# Iridium_9603_Beacon.net
KiCad netlist of a schematic drawn in EAGLE
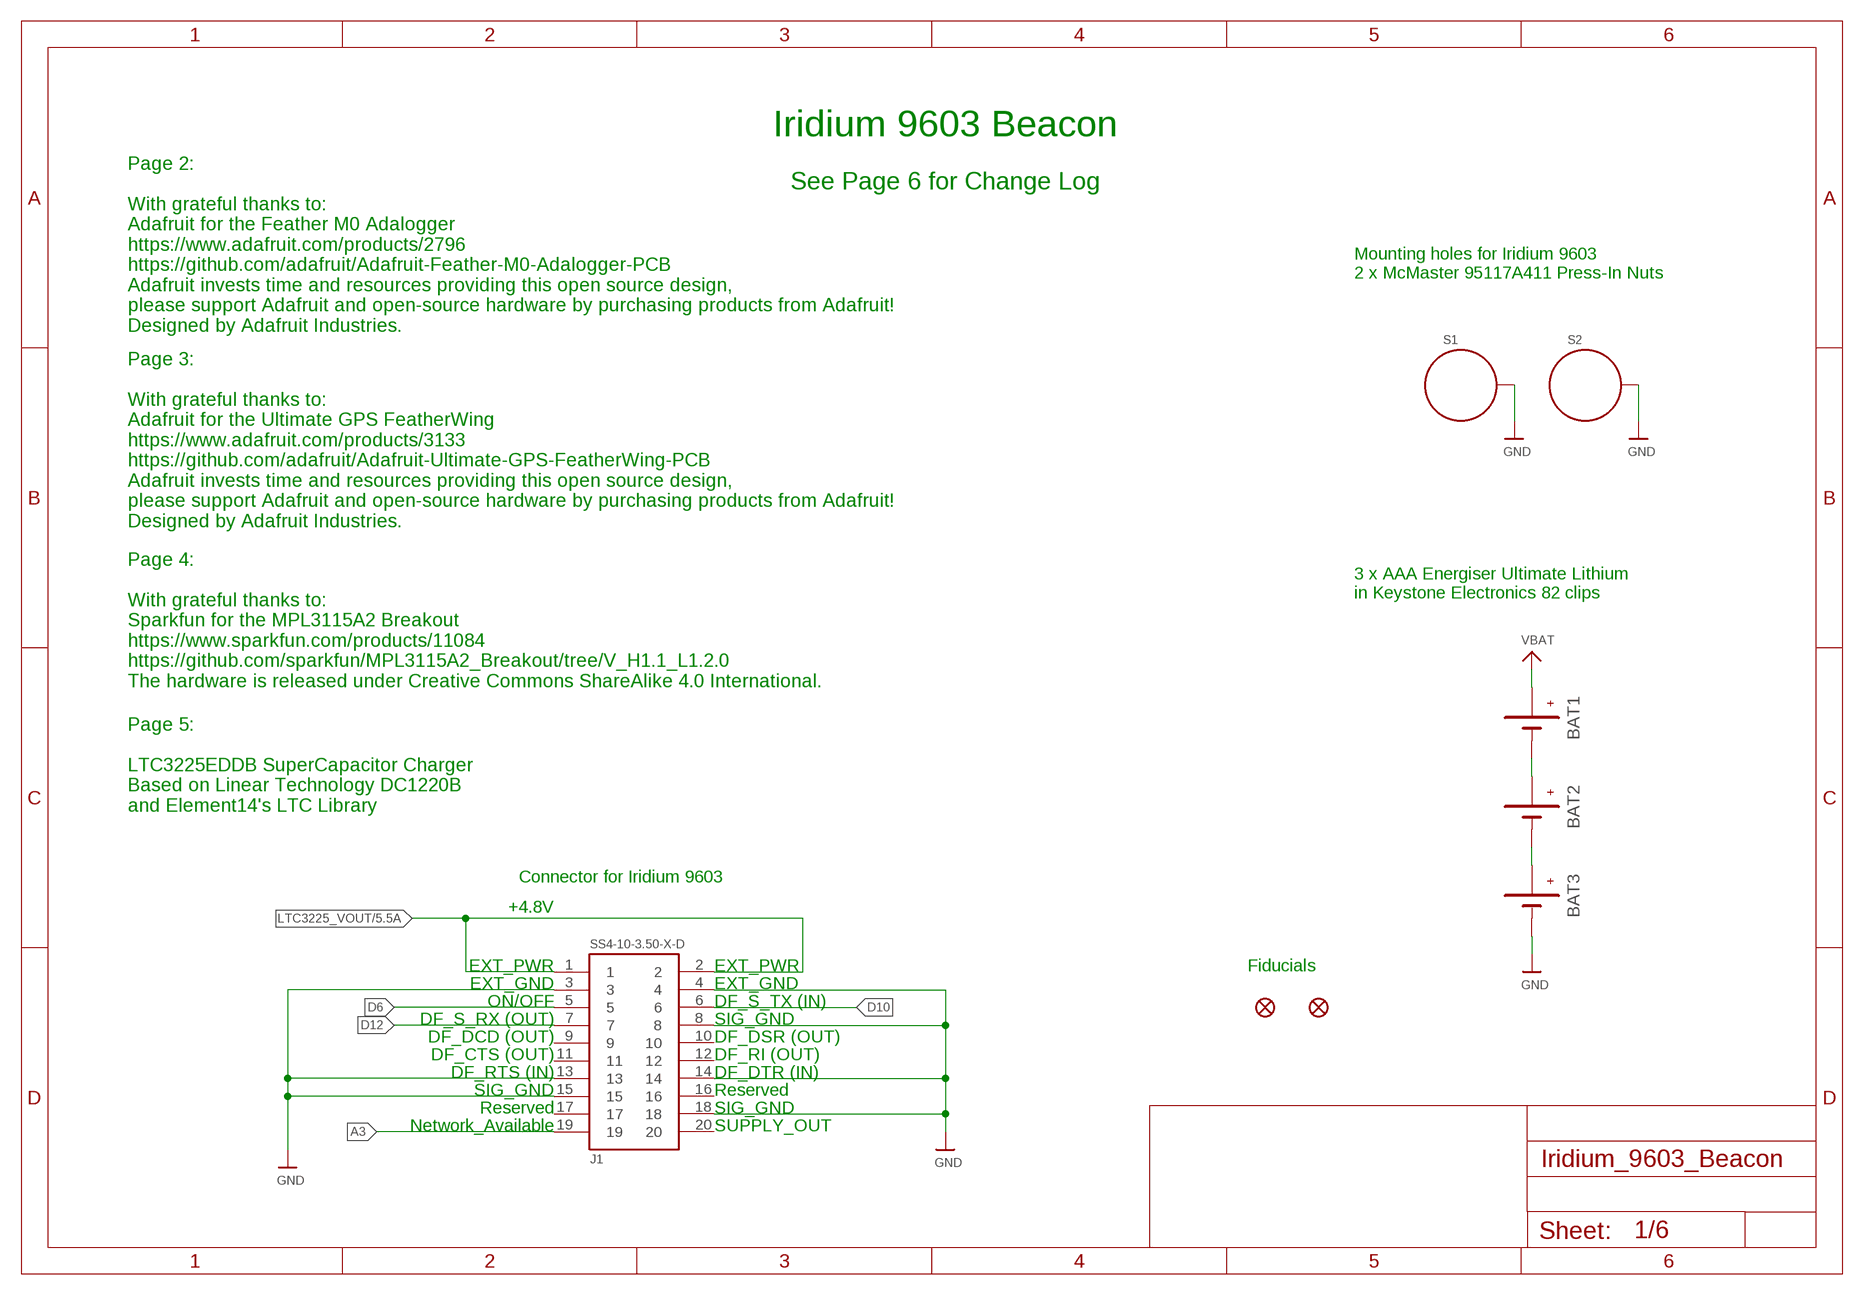
[diagram p0: schematic, sheet 1]
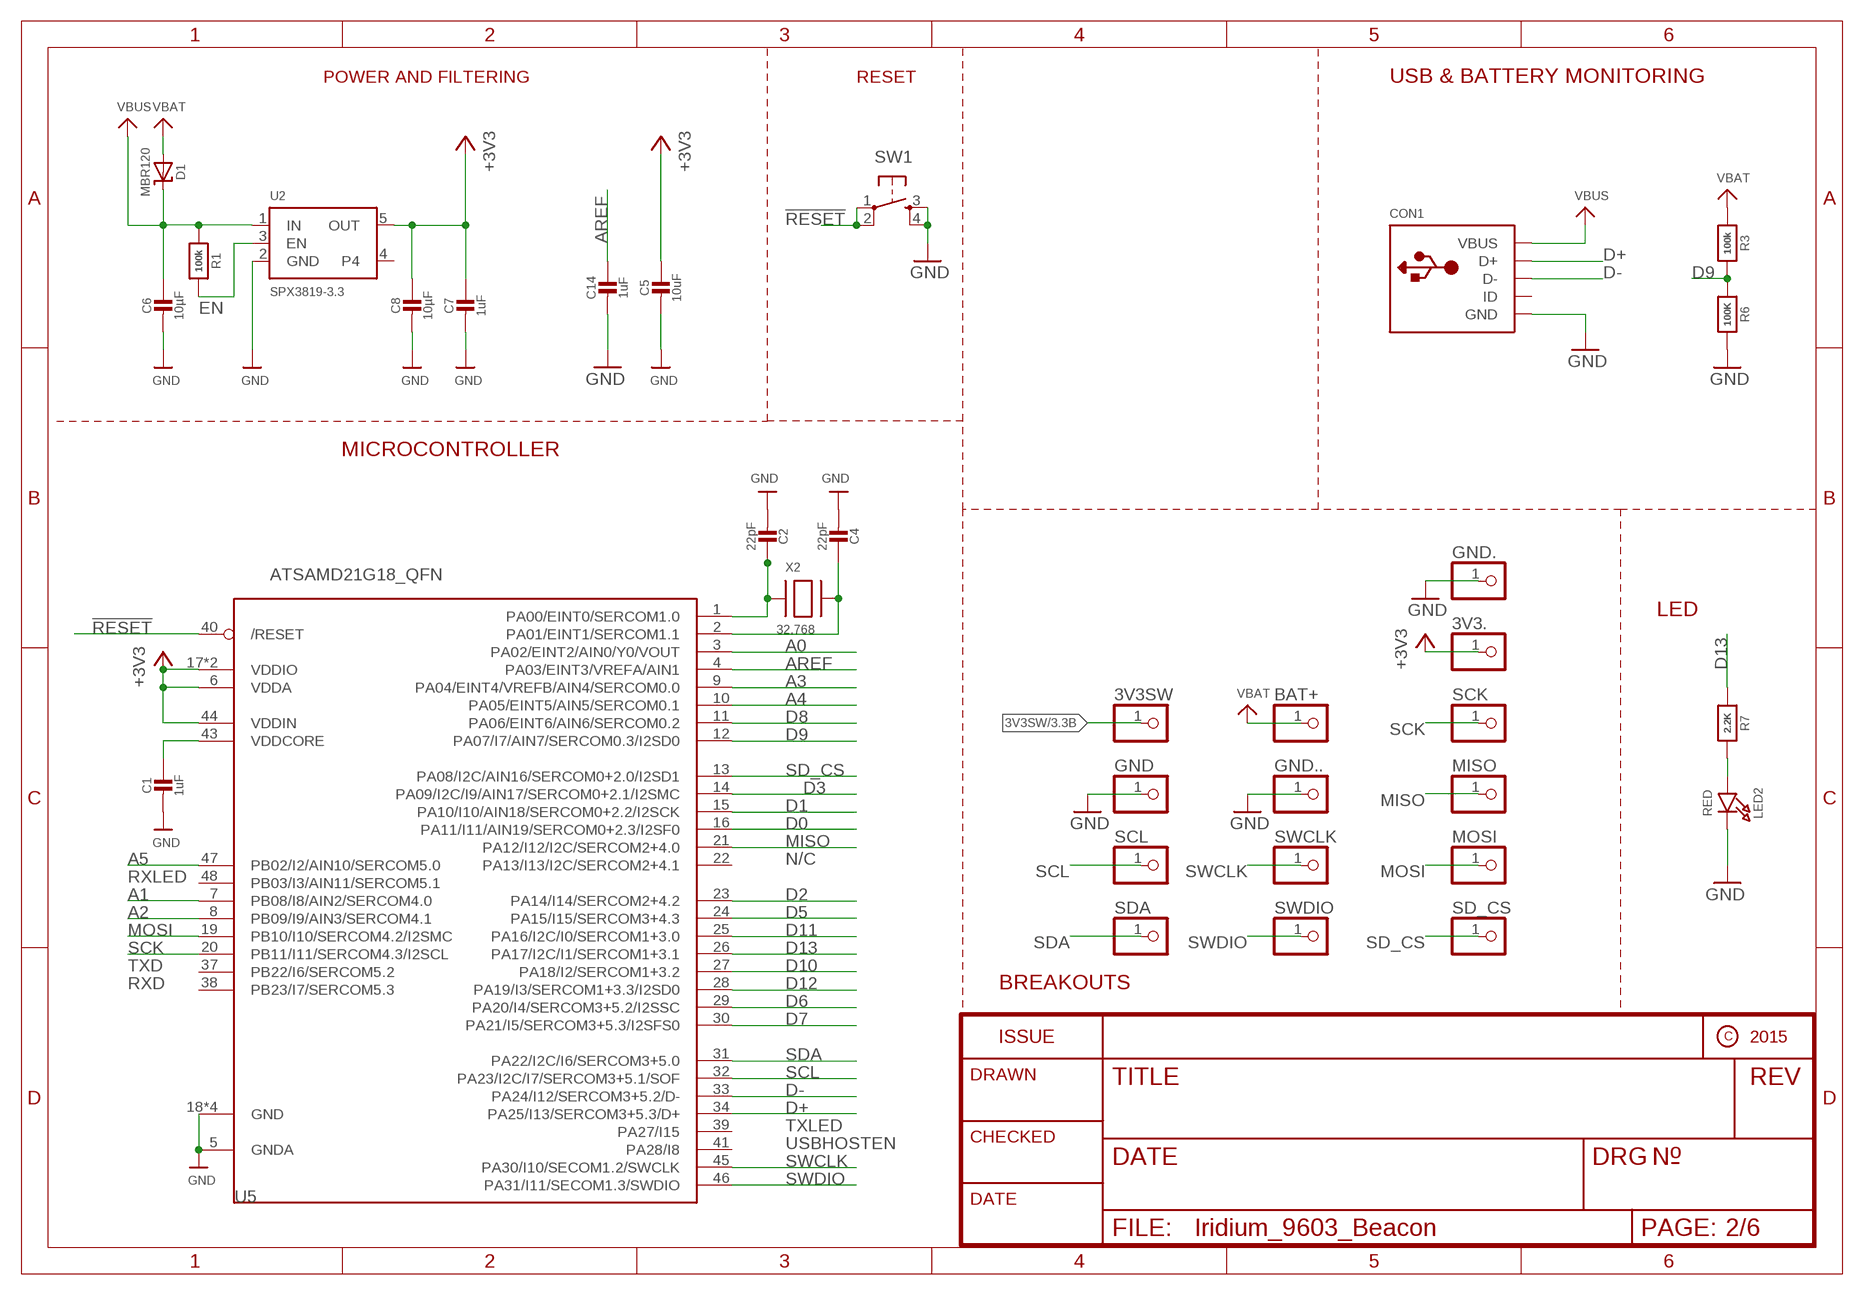
[diagram p1: schematic, sheet 2]
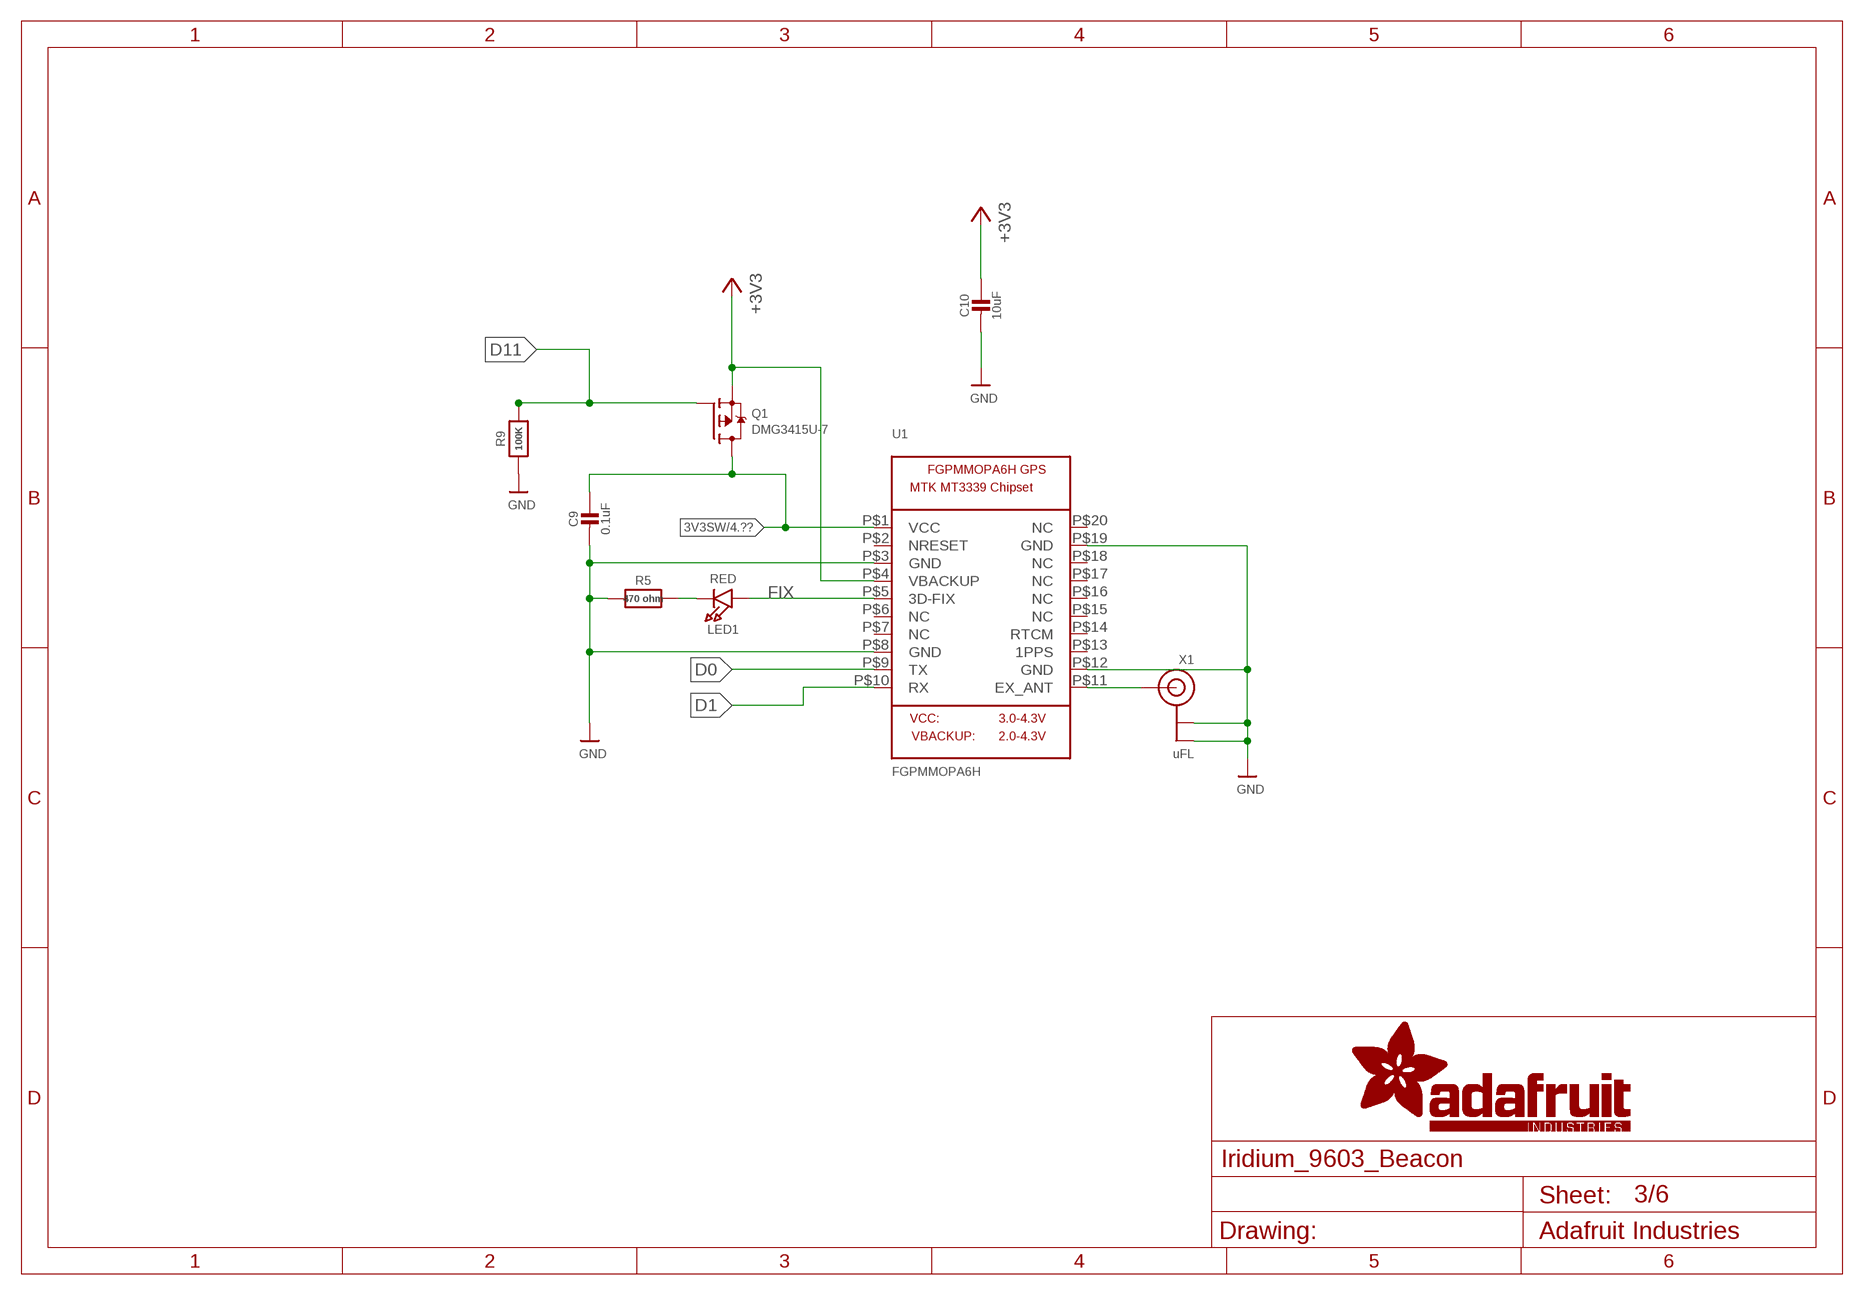
[diagram p2: schematic, sheet 3]
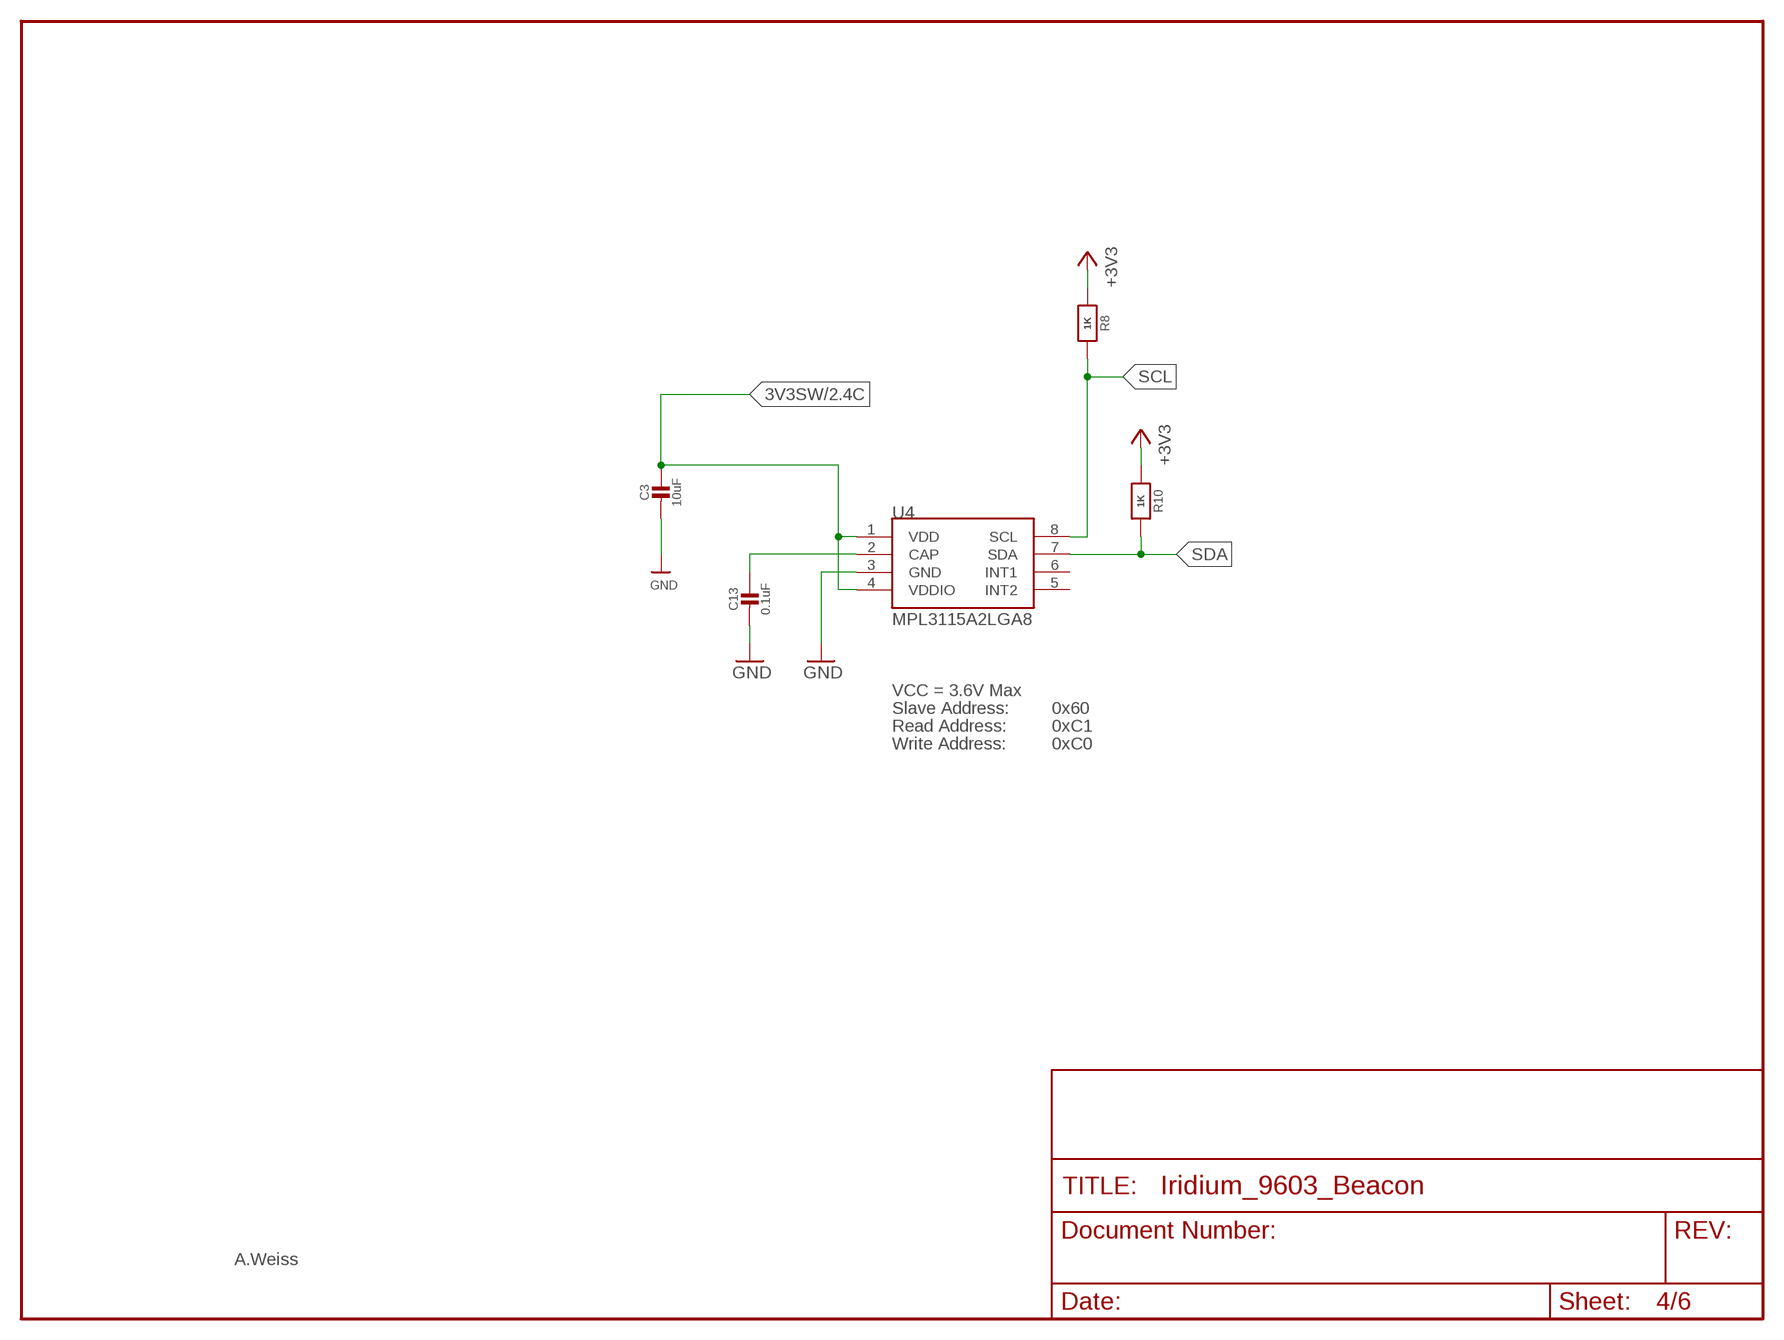
[diagram p3: schematic, sheet 4]
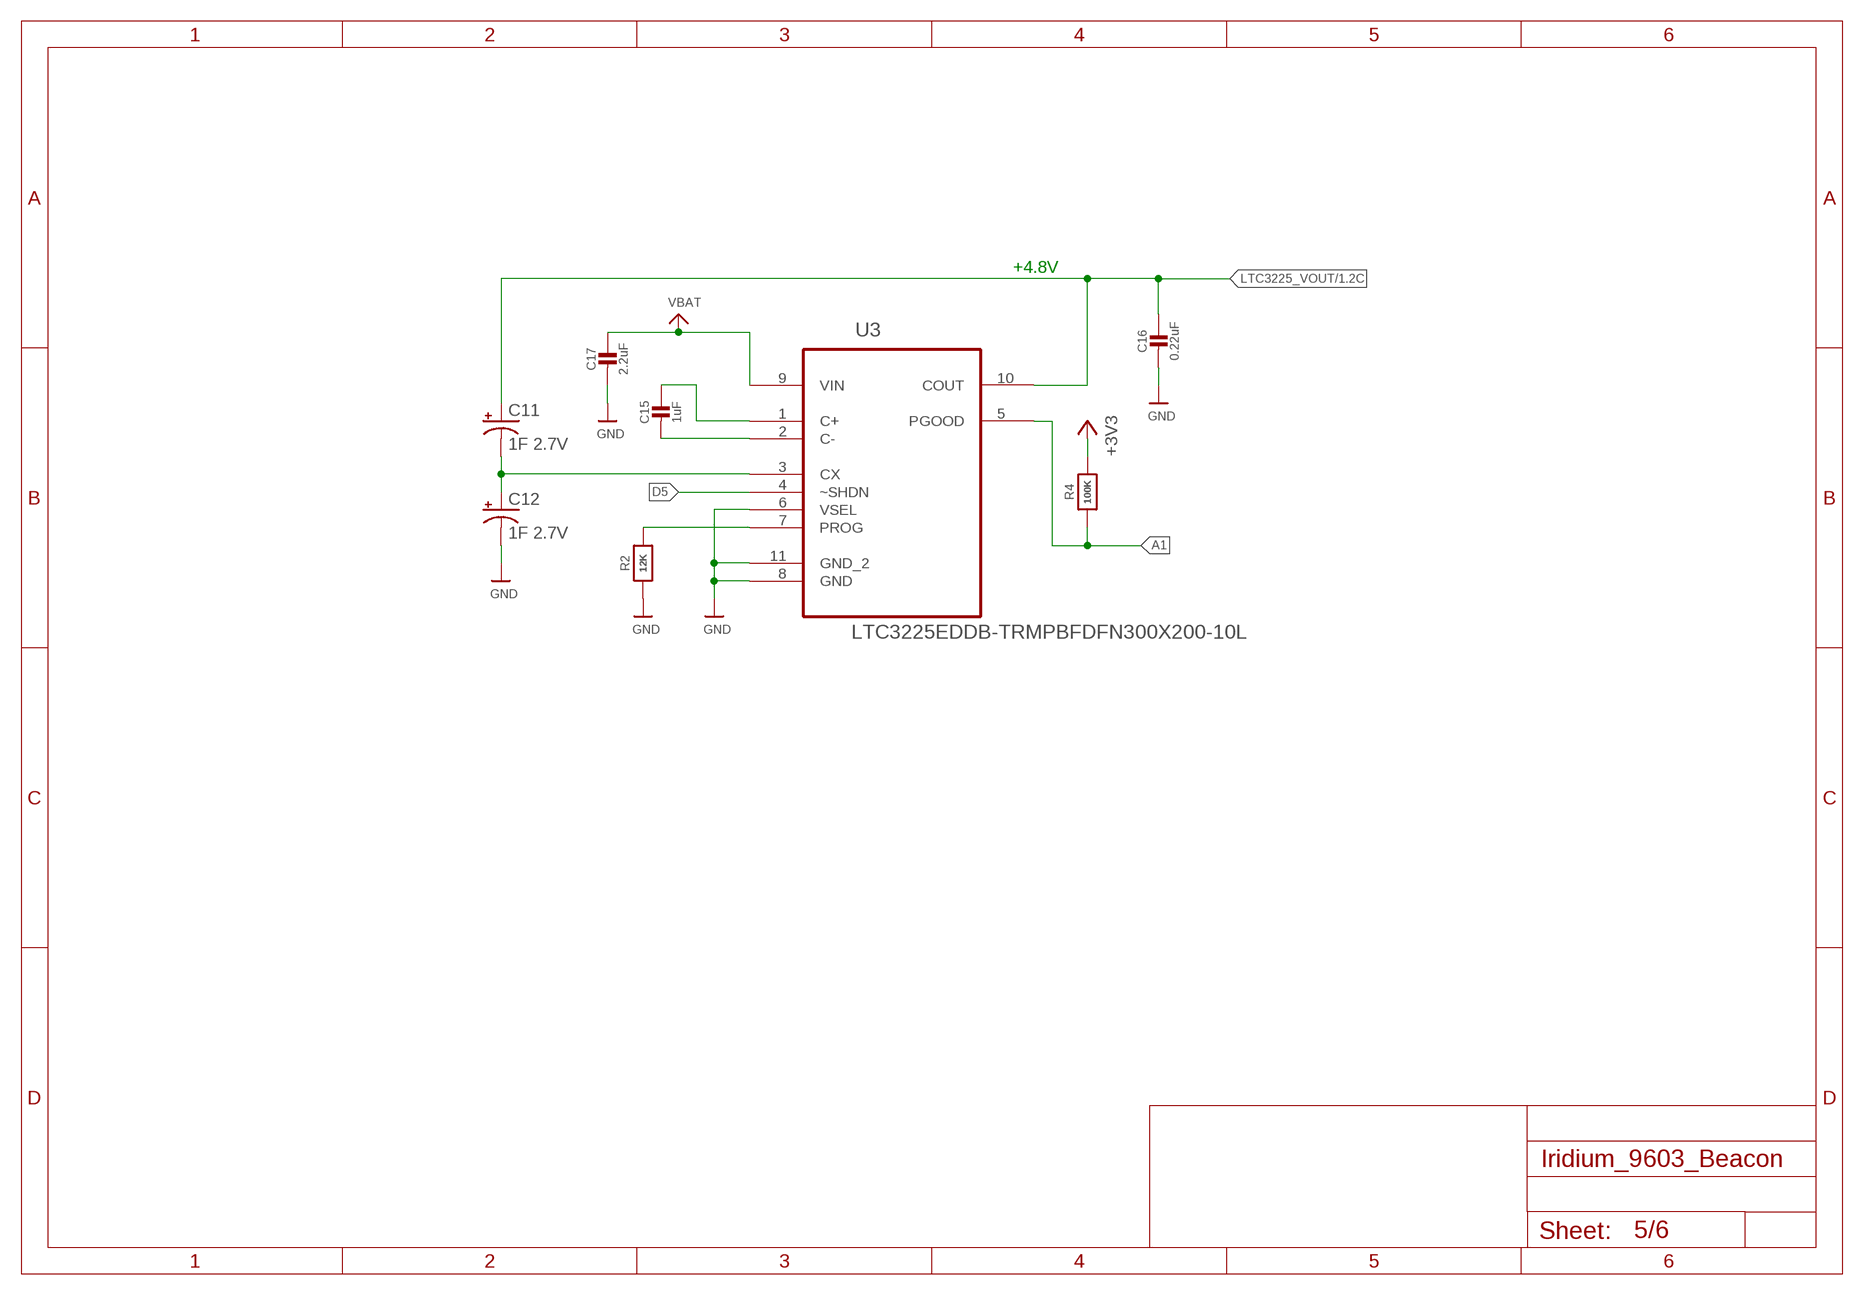
[diagram p4: schematic, sheet 5]
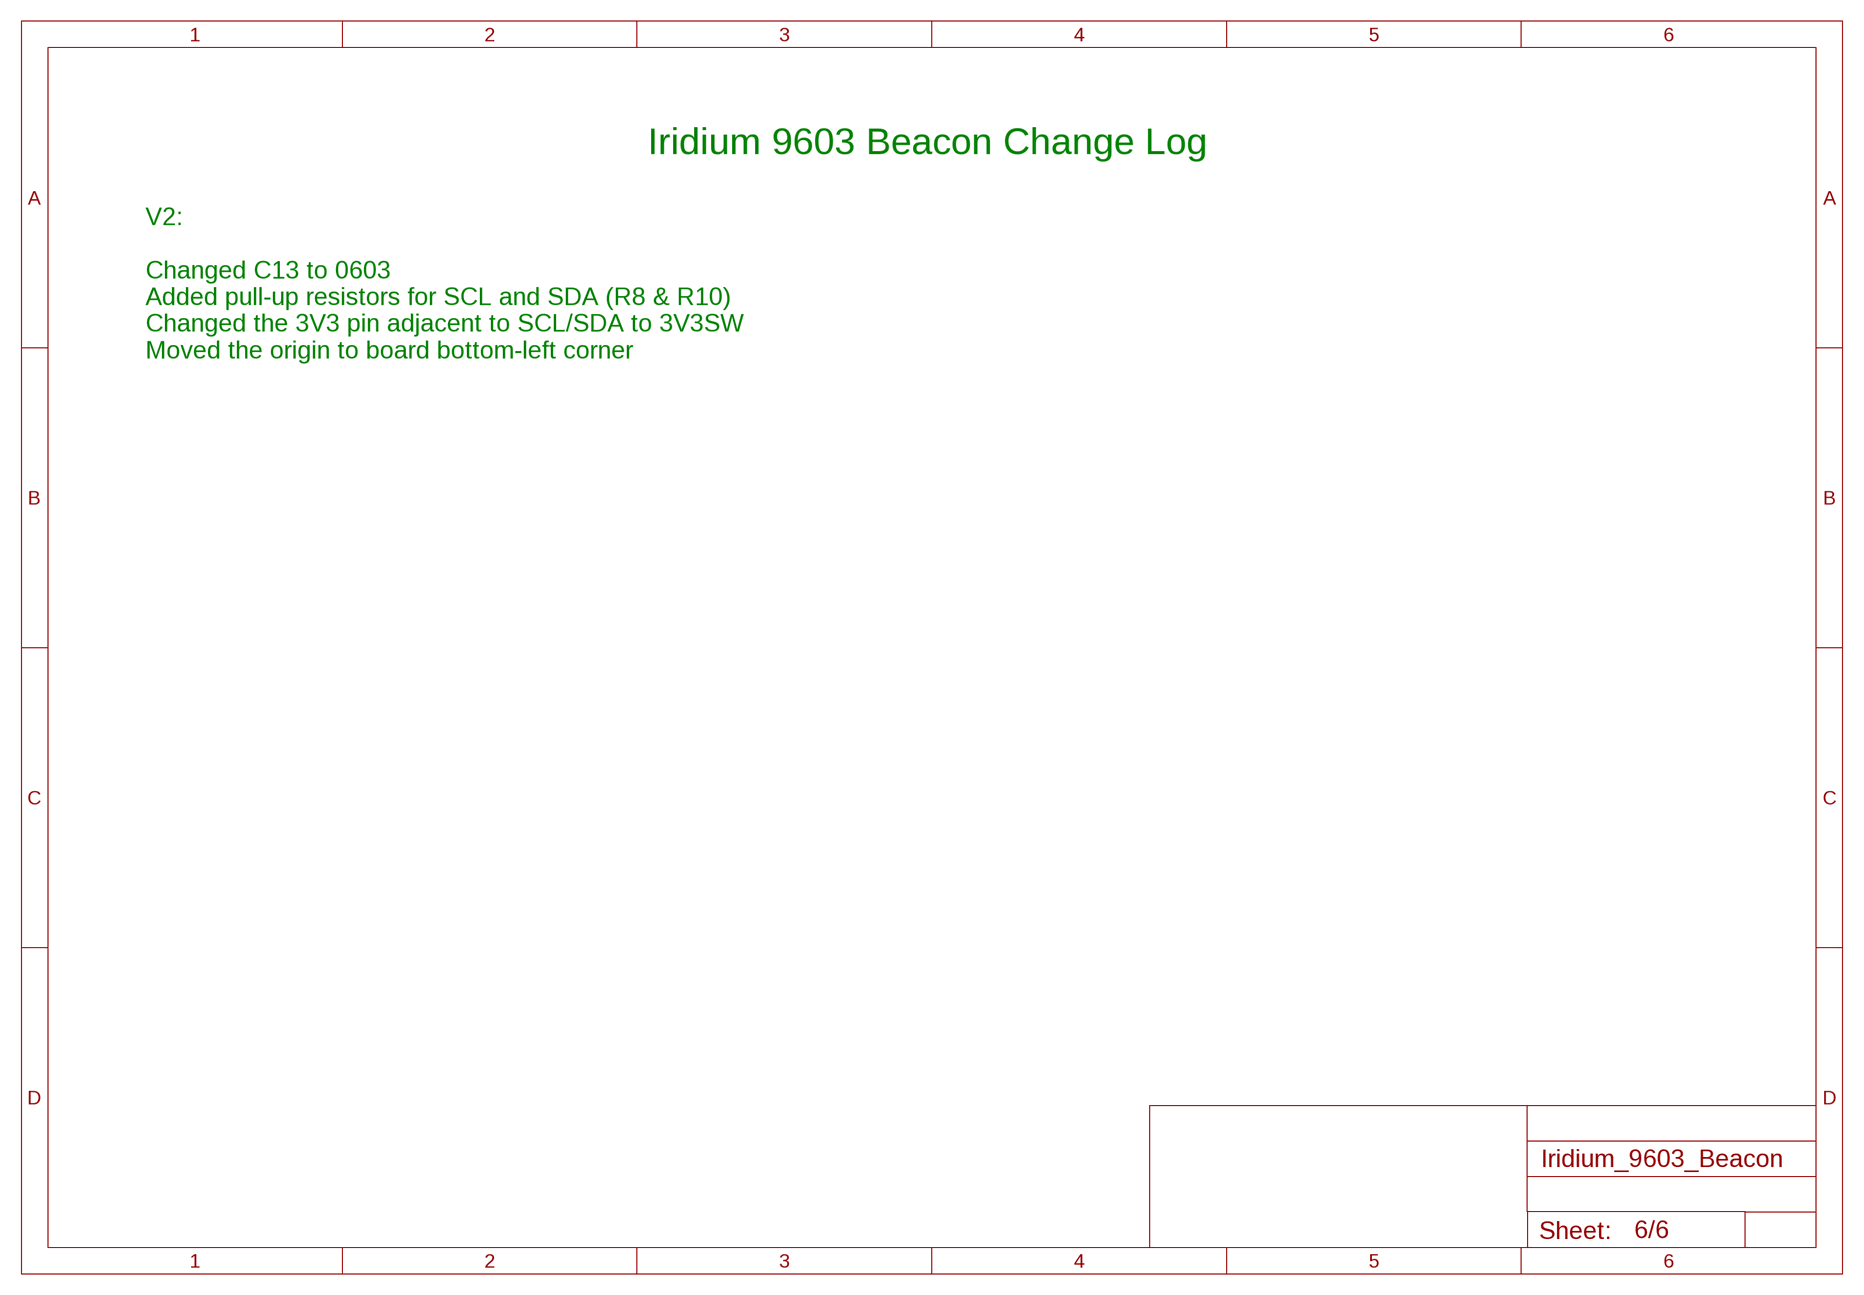
[diagram p5: schematic, sheet 6]

(export (version "E")
  (design (tool "Eeschema 10.0.6"))
  (components
    (comp (ref "C9")
      (value "0.1uF")
      (footprint "eagle-import:0805-NO")
      (libsource (lib "eagle-import") (part "CAP_CERAMIC0805-NOOUTLINE"))
    )
    (comp (ref "C10")
      (value "10uF")
      (footprint "eagle-import:0805-NO")
      (libsource (lib "eagle-import") (part "CAP_CERAMIC0805-NOOUTLINE"))
    )
    (comp (ref "LED1")
      (value "RED")
      (footprint "eagle-import:CHIPLED_0805_NOOUTLINE")
      (libsource (lib "eagle-import") (part "LED0805_NOOUTLINE"))
    )
    (comp (ref "Q1")
      (value "DMG3415U-7")
      (footprint "eagle-import:SOT23-WIDE")
      (libsource (lib "eagle-import") (part "MOSFET-PWIDE"))
    )
    (comp (ref "R5")
      (value "470 ohm")
      (footprint "eagle-import:0805-NO")
      (libsource (lib "eagle-import") (part "RESISTOR0805_NOOUTLINE"))
    )
    (comp (ref "R9")
      (value "100K")
      (footprint "eagle-import:0805-NO")
      (libsource (lib "eagle-import") (part "RESISTOR0805_NOOUTLINE"))
    )
    (comp (ref "U1")
      (value "FGPMMOPA6H")
      (footprint "eagle-import:FGPMMOPA6H")
      (libsource (lib "eagle-import") (part "GPS_FGPMMOPA6H"))
    )
    (comp (ref "X1")
      (value "uFL")
      (footprint "eagle-import:U.FL")
      (libsource (lib "eagle-import") (part "ANTENNA_U.FL"))
    )
    (comp (ref "C11")
      (value "1F 2.7V")
      (footprint "eagle-import:CPOL-RADIAL-1F-2.7V")
      (libsource (lib "eagle-import") (part "1F-2.7V(PTH)CPOL-RADIAL-1H-2.7V"))
    )
    (comp (ref "C12")
      (value "1F 2.7V")
      (footprint "eagle-import:CPOL-RADIAL-1F-2.7V")
      (libsource (lib "eagle-import") (part "1F-2.7V(PTH)CPOL-RADIAL-1H-2.7V"))
    )
    (comp (ref "C15")
      (value "1uF")
      (footprint "eagle-import:0603-NO")
      (libsource (lib "eagle-import") (part "CAP_CERAMIC0603_NO"))
    )
    (comp (ref "C16")
      (value "0.22uF")
      (footprint "eagle-import:0603-NO")
      (libsource (lib "eagle-import") (part "CAP_CERAMIC0603_NO"))
    )
    (comp (ref "C17")
      (value "2.2uF")
      (footprint "eagle-import:0805-NO")
      (libsource (lib "eagle-import") (part "CAP_CERAMIC0805-NOOUTLINE"))
    )
    (comp (ref "R2")
      (value "12K")
      (footprint "eagle-import:0805-NO")
      (libsource (lib "eagle-import") (part "RESISTOR0805_NOOUTLINE"))
    )
    (comp (ref "R4")
      (value "100K")
      (footprint "eagle-import:0805-NO")
      (libsource (lib "eagle-import") (part "RESISTOR0805_NOOUTLINE"))
    )
    (comp (ref "U3")
      (value "LTC3225EDDB-TRMPBFDFN300X200-10L")
      (footprint "eagle-import:DFN300X200-10L")
      (libsource (lib "eagle-import") (part "LTC3225EDDB-TRMPBFDFN300X200-10L"))
    )
    (comp (ref "3V3.")
      (value "PINHD-1X1")
      (footprint "eagle-import:1X01")
      (libsource (lib "eagle-import") (part "PINHD-1X1"))
    )
    (comp (ref "3V3SW")
      (value "PINHD-1X1")
      (footprint "eagle-import:1X01")
      (libsource (lib "eagle-import") (part "PINHD-1X1"))
    )
    (comp (ref "BAT+")
      (value "PINHD-1X1")
      (footprint "eagle-import:1X01")
      (libsource (lib "eagle-import") (part "PINHD-1X1"))
    )
    (comp (ref "C1")
      (value "1uF")
      (footprint "eagle-import:0603-NO")
      (libsource (lib "eagle-import") (part "CAP_CERAMIC0603_NO"))
    )
    (comp (ref "C2")
      (value "22pF")
      (footprint "eagle-import:0603-NO")
      (libsource (lib "eagle-import") (part "CAP_CERAMIC0603_NO"))
    )
    (comp (ref "C4")
      (value "22pF")
      (footprint "eagle-import:0603-NO")
      (libsource (lib "eagle-import") (part "CAP_CERAMIC0603_NO"))
    )
    (comp (ref "C5")
      (value "10uF")
      (footprint "eagle-import:0805-NO")
      (libsource (lib "eagle-import") (part "CAP_CERAMIC0805-NOOUTLINE"))
    )
    (comp (ref "C6")
      (value "10µF")
      (footprint "eagle-import:0805-NO")
      (libsource (lib "eagle-import") (part "CAP_CERAMIC0805-NOOUTLINE"))
    )
    (comp (ref "C7")
      (value "1uF")
      (footprint "eagle-import:0603-NO")
      (libsource (lib "eagle-import") (part "CAP_CERAMIC0603_NO"))
    )
    (comp (ref "C8")
      (value "10µF")
      (footprint "eagle-import:0805-NO")
      (libsource (lib "eagle-import") (part "CAP_CERAMIC0805-NOOUTLINE"))
    )
    (comp (ref "C14")
      (value "1uF")
      (footprint "eagle-import:0603-NO")
      (libsource (lib "eagle-import") (part "CAP_CERAMIC0603_NO"))
    )
    (comp (ref "CON1")
      (value "USBFCI_10103594")
      (footprint "eagle-import:FCI_10103594")
      (libsource (lib "eagle-import") (part "USBFCI_10103594"))
    )
    (comp (ref "D1")
      (value "MBR120")
      (footprint "eagle-import:SOD-123")
      (libsource (lib "eagle-import") (part "DIODE-SCHOTTKYSOD-123"))
    )
    (comp (ref "GND")
      (value "PINHD-1X1")
      (footprint "eagle-import:1X01")
      (libsource (lib "eagle-import") (part "PINHD-1X1"))
    )
    (comp (ref "GND.")
      (value "PINHD-1X1")
      (footprint "eagle-import:1X01")
      (libsource (lib "eagle-import") (part "PINHD-1X1"))
    )
    (comp (ref "GND..")
      (value "PINHD-1X1")
      (footprint "eagle-import:1X01")
      (libsource (lib "eagle-import") (part "PINHD-1X1"))
    )
    (comp (ref "LED2")
      (value "RED")
      (footprint "eagle-import:CHIPLED_0805_NOOUTLINE")
      (libsource (lib "eagle-import") (part "LED0805_NOOUTLINE"))
    )
    (comp (ref "MISO")
      (value "PINHD-1X1")
      (footprint "eagle-import:1X01")
      (libsource (lib "eagle-import") (part "PINHD-1X1"))
    )
    (comp (ref "MOSI")
      (value "PINHD-1X1")
      (footprint "eagle-import:1X01")
      (libsource (lib "eagle-import") (part "PINHD-1X1"))
    )
    (comp (ref "R1")
      (value "100k")
      (footprint "eagle-import:0603-NO")
      (libsource (lib "eagle-import") (part "RESISTOR_0603_NOOUT"))
    )
    (comp (ref "R3")
      (value "100k")
      (footprint "eagle-import:0603-NO")
      (libsource (lib "eagle-import") (part "RESISTOR_0603_NOOUT"))
    )
    (comp (ref "R6")
      (value "100K")
      (footprint "eagle-import:0603-NO")
      (libsource (lib "eagle-import") (part "RESISTOR_0603_NOOUT"))
    )
    (comp (ref "R7")
      (value "2.2K")
      (footprint "eagle-import:0603-NO")
      (libsource (lib "eagle-import") (part "RESISTOR_0603_NOOUT"))
    )
    (comp (ref "SCK")
      (value "PINHD-1X1")
      (footprint "eagle-import:1X01")
      (libsource (lib "eagle-import") (part "PINHD-1X1"))
    )
    (comp (ref "SCL")
      (value "PINHD-1X1")
      (footprint "eagle-import:1X01")
      (libsource (lib "eagle-import") (part "PINHD-1X1"))
    )
    (comp (ref "SDA")
      (value "PINHD-1X1")
      (footprint "eagle-import:1X01")
      (libsource (lib "eagle-import") (part "PINHD-1X1"))
    )
    (comp (ref "SD_CS")
      (value "PINHD-1X1")
      (footprint "eagle-import:1X01")
      (libsource (lib "eagle-import") (part "PINHD-1X1"))
    )
    (comp (ref "SW1")
      (value "SWITCH_SPST_4_PINRECT")
      (footprint "eagle-import:TACTILE_SWITCH_SMD_4.6X2.8MM")
      (libsource (lib "eagle-import") (part "SWITCH_SPST_4_PINRECT"))
    )
    (comp (ref "SWCLK")
      (value "PINHD-1X1")
      (footprint "eagle-import:1X01")
      (libsource (lib "eagle-import") (part "PINHD-1X1"))
    )
    (comp (ref "SWDIO")
      (value "PINHD-1X1")
      (footprint "eagle-import:1X01")
      (libsource (lib "eagle-import") (part "PINHD-1X1"))
    )
    (comp (ref "U2")
      (value "SPX3819-3.3")
      (footprint "eagle-import:SOT23-5")
      (libsource (lib "eagle-import") (part "VREG_SOT23-5"))
    )
    (comp (ref "U5")
      (value "ATSAMD21G18_QFN")
      (footprint "eagle-import:TQFN48_7MM")
      (libsource (lib "eagle-import") (part "ATSAMD21J_QFN"))
    )
    (comp (ref "X2")
      (value "32.768")
      (footprint "eagle-import:XTAL3215")
      (libsource (lib "eagle-import") (part "XTAL-3.2X1.5"))
    )
    (comp (ref "C3")
      (value "10uF")
      (footprint "eagle-import:0805-NO")
      (libsource (lib "eagle-import") (part "CAP_CERAMIC0805-NOOUTLINE"))
    )
    (comp (ref "C13")
      (value "0.1uF")
      (footprint "eagle-import:0603-NO")
      (libsource (lib "eagle-import") (part "CAP_CERAMIC0603_NO"))
    )
    (comp (ref "R8")
      (value "1K")
      (footprint "eagle-import:0603-NO")
      (libsource (lib "eagle-import") (part "RESISTOR_0603_NOOUT"))
    )
    (comp (ref "R10")
      (value "1K")
      (footprint "eagle-import:0603-NO")
      (libsource (lib "eagle-import") (part "RESISTOR_0603_NOOUT"))
    )
    (comp (ref "U4")
      (value "MPL3115A2LGA8")
      (footprint "eagle-import:LGA8")
      (libsource (lib "eagle-import") (part "MPL3115A2LGA8"))
    )
    (comp (ref "BAT1")
      (value "BATTERYKEYSTONE82")
      (footprint "eagle-import:BATTERY-AAA-KEYSTONE82")
      (libsource (lib "eagle-import") (part "BATTERYKEYSTONE82"))
    )
    (comp (ref "BAT2")
      (value "BATTERYKEYSTONE82")
      (footprint "eagle-import:BATTERY-AAA-KEYSTONE82")
      (libsource (lib "eagle-import") (part "BATTERYKEYSTONE82"))
    )
    (comp (ref "BAT3")
      (value "BATTERYKEYSTONE82")
      (footprint "eagle-import:BATTERY-AAA-KEYSTONE82")
      (libsource (lib "eagle-import") (part "BATTERYKEYSTONE82"))
    )
    (comp (ref "FD1")
      (value "FIDUCIAL1X2")
      (footprint "eagle-import:FIDUCIAL-1X2")
      (libsource (lib "eagle-import") (part "FIDUCIAL1X2"))
    )
    (comp (ref "FD2")
      (value "FIDUCIAL1X2")
      (footprint "eagle-import:FIDUCIAL-1X2")
      (libsource (lib "eagle-import") (part "FIDUCIAL1X2"))
    )
    (comp (ref "J1")
      (value "SS4-10-3.50-X-D")
      (footprint "eagle-import:SS4-10-3.50-X-D")
      (libsource (lib "eagle-import") (part "SS4-10-3.50-X-D"))
    )
    (comp (ref "S1")
      (value "STANDOFF_ELECTRICALMCMASTER-95117A411")
      (footprint "eagle-import:STANDOFF-ELECTRICAL-MCMASTER-95117A411")
      (libsource (lib "eagle-import") (part "STANDOFF_ELECTRICALMCMASTER-95117A411"))
    )
    (comp (ref "S2")
      (value "STANDOFF_ELECTRICALMCMASTER-95117A411")
      (footprint "eagle-import:STANDOFF-ELECTRICAL-MCMASTER-95117A411")
      (libsource (lib "eagle-import") (part "STANDOFF_ELECTRICALMCMASTER-95117A411"))
    )
  )
  (nets
    (net (code "1") (name "+3V3") (class "Default")
      (node (ref "3V3.") (pin "1") (pinfunction "1_1") (pintype "passive"))
      (node (ref "C10") (pin "1") (pinfunction "1_1") (pintype "passive"))
      (node (ref "C5") (pin "1") (pinfunction "1_1") (pintype "passive"))
      (node (ref "C7") (pin "1") (pinfunction "1_1") (pintype "passive"))
      (node (ref "C8") (pin "1") (pinfunction "1_1") (pintype "passive"))
      (node (ref "Q1") (pin "2") (pinfunction "S_2") (pintype "passive"))
      (node (ref "R10") (pin "1") (pinfunction "1_1") (pintype "passive"))
      (node (ref "R4") (pin "2") (pinfunction "2_2") (pintype "passive"))
      (node (ref "R8") (pin "1") (pinfunction "1_1") (pintype "passive"))
      (node (ref "U1") (pin "P$4") (pinfunction "VBACKUP_P$4") (pintype "bidirectional"))
      (node (ref "U2") (pin "5") (pinfunction "OUT_5") (pintype "power_in"))
      (node (ref "U5") (pin "17") (pinfunction "VDDIO_17") (pintype "power_in"))
      (node (ref "U5") (pin "36") (pinfunction "VDDIO_36") (pintype "power_in"))
      (node (ref "U5") (pin "44") (pinfunction "VDDIN_44") (pintype "power_in"))
      (node (ref "U5") (pin "6") (pinfunction "VDDA_6") (pintype "power_in"))
    )
    (net (code "2") (name "3V3SW") (class "Default")
      (node (ref "3V3SW") (pin "1") (pinfunction "1_1") (pintype "passive"))
      (node (ref "C3") (pin "1") (pinfunction "1_1") (pintype "passive"))
      (node (ref "C9") (pin "1") (pinfunction "1_1") (pintype "passive"))
      (node (ref "Q1") (pin "3") (pinfunction "D_3") (pintype "passive"))
      (node (ref "U1") (pin "P$1") (pinfunction "VCC_P$1") (pintype "bidirectional"))
      (node (ref "U4") (pin "1") (pinfunction "VDD_1") (pintype "bidirectional"))
      (node (ref "U4") (pin "4") (pinfunction "VDDIO_4") (pintype "bidirectional"))
    )
    (net (code "3") (name "A0") (class "Default")
      (node (ref "U5") (pin "3") (pinfunction "PA02/EINT2/AIN0/Y0/VOUT_3") (pintype "bidirectional"))
    )
    (net (code "4") (name "A1") (class "Default")
      (node (ref "R4") (pin "1") (pinfunction "1_1") (pintype "passive"))
      (node (ref "U3") (pin "5") (pinfunction "PGOOD_5") (pintype "output"))
      (node (ref "U5") (pin "7") (pinfunction "PB08/I8/AIN2/SERCOM4.0_7") (pintype "bidirectional"))
    )
    (net (code "5") (name "A2") (class "Default")
      (node (ref "U5") (pin "8") (pinfunction "PB09/I9/AIN3/SERCOM4.1_8") (pintype "bidirectional"))
    )
    (net (code "6") (name "A3") (class "Default")
      (node (ref "J1") (pin "19") (pinfunction "19_19") (pintype "bidirectional"))
      (node (ref "U5") (pin "9") (pinfunction "PA04/EINT4/VREFB/AIN4/SERCOM0.0_9") (pintype "bidirectional"))
    )
    (net (code "7") (name "A4") (class "Default")
      (node (ref "U5") (pin "10") (pinfunction "PA05/EINT5/AIN5/SERCOM0.1_10") (pintype "bidirectional"))
    )
    (net (code "8") (name "A5") (class "Default")
      (node (ref "U5") (pin "47") (pinfunction "PB02/I2/AIN10/SERCOM5.0_47") (pintype "bidirectional"))
    )
    (net (code "9") (name "AREF") (class "Default")
      (node (ref "C14") (pin "1") (pinfunction "1_1") (pintype "passive"))
      (node (ref "U5") (pin "4") (pinfunction "PA03/EINT3/VREFA/AIN1_4") (pintype "bidirectional"))
    )
    (net (code "10") (name "D+") (class "Default")
      (node (ref "CON1") (pin "D+") (pinfunction "D+_D+") (pintype "bidirectional"))
      (node (ref "U5") (pin "34") (pinfunction "PA25/I13/SERCOM3+5.3/D+_34") (pintype "bidirectional"))
    )
    (net (code "11") (name "D-") (class "Default")
      (node (ref "CON1") (pin "D-") (pinfunction "D-_D-") (pintype "bidirectional"))
      (node (ref "U5") (pin "33") (pinfunction "PA24/I12/SERCOM3+5.2/D-_33") (pintype "bidirectional"))
    )
    (net (code "12") (name "D0") (class "Default")
      (node (ref "U1") (pin "P$9") (pinfunction "TX_P$9") (pintype "bidirectional"))
      (node (ref "U5") (pin "16") (pinfunction "PA11/I11/AIN19/SERCOM0+2.3/I2SF0_16") (pintype "bidirectional"))
    )
    (net (code "13") (name "D1") (class "Default")
      (node (ref "U1") (pin "P$10") (pinfunction "RX_P$10") (pintype "bidirectional"))
      (node (ref "U5") (pin "15") (pinfunction "PA10/I10/AIN18/SERCOM0+2.2/I2SCK_15") (pintype "bidirectional"))
    )
    (net (code "14") (name "D2") (class "Default")
      (node (ref "U5") (pin "23") (pinfunction "PA14/I14/SERCOM2+4.2_23") (pintype "bidirectional"))
    )
    (net (code "15") (name "D3") (class "Default")
      (node (ref "U5") (pin "14") (pinfunction "PA09/I2C/I9/AIN17/SERCOM0+2.1/I2SMC_14") (pintype "bidirectional"))
    )
    (net (code "16") (name "D5") (class "Default")
      (node (ref "U3") (pin "4") (pinfunction "~{SHDN}_4") (pintype "input"))
      (node (ref "U5") (pin "24") (pinfunction "PA15/I15/SERCOM3+4.3_24") (pintype "bidirectional"))
    )
    (net (code "17") (name "D6") (class "Default")
      (node (ref "J1") (pin "5") (pinfunction "5_5") (pintype "bidirectional"))
      (node (ref "U5") (pin "29") (pinfunction "PA20/I4/SERCOM3+5.2/I2SSC_29") (pintype "bidirectional"))
    )
    (net (code "18") (name "D7") (class "Default")
      (node (ref "U5") (pin "30") (pinfunction "PA21/I5/SERCOM3+5.3/I2SFS0_30") (pintype "bidirectional"))
    )
    (net (code "19") (name "D8") (class "Default")
      (node (ref "U5") (pin "11") (pinfunction "PA06/EINT6/AIN6/SERCOM0.2_11") (pintype "bidirectional"))
    )
    (net (code "20") (name "D9") (class "Default")
      (node (ref "R3") (pin "2") (pinfunction "2_2") (pintype "passive"))
      (node (ref "R6") (pin "1") (pinfunction "1_1") (pintype "passive"))
      (node (ref "U5") (pin "12") (pinfunction "PA07/I7/AIN7/SERCOM0.3/I2SD0_12") (pintype "bidirectional"))
    )
    (net (code "21") (name "D10") (class "Default")
      (node (ref "J1") (pin "6") (pinfunction "6_6") (pintype "bidirectional"))
      (node (ref "U5") (pin "27") (pinfunction "PA18/I2/SERCOM1+3.2_27") (pintype "bidirectional"))
    )
    (net (code "22") (name "D11") (class "Default")
      (node (ref "Q1") (pin "1") (pinfunction "G_1") (pintype "passive"))
      (node (ref "R9") (pin "2") (pinfunction "2_2") (pintype "passive"))
      (node (ref "U5") (pin "25") (pinfunction "PA16/I2C/I0/SERCOM1+3.0_25") (pintype "bidirectional"))
    )
    (net (code "23") (name "D12") (class "Default")
      (node (ref "J1") (pin "7") (pinfunction "7_7") (pintype "bidirectional"))
      (node (ref "U5") (pin "28") (pinfunction "PA19/I3/SERCOM1+3.3/I2SD0_28") (pintype "bidirectional"))
    )
    (net (code "24") (name "D13") (class "Default")
      (node (ref "R7") (pin "1") (pinfunction "1_1") (pintype "passive"))
      (node (ref "U5") (pin "26") (pinfunction "PA17/I2C/I1/SERCOM1+3.1_26") (pintype "bidirectional"))
    )
    (net (code "25") (name "EN") (class "Default")
      (node (ref "R1") (pin "2") (pinfunction "2_2") (pintype "passive"))
      (node (ref "U2") (pin "3") (pinfunction "EN_3") (pintype "input"))
    )
    (net (code "26") (name "FIX") (class "Default")
      (node (ref "LED1") (pin "A") (pinfunction "A_A") (pintype "passive"))
      (node (ref "U1") (pin "P$5") (pinfunction "3D-FIX_P$5") (pintype "bidirectional"))
    )
    (net (code "27") (name "GND") (class "Default")
      (node (ref "BAT3") (pin "GND@1") (pinfunction "-_GND@1") (pintype "power_in"))
      (node (ref "BAT3") (pin "GND@2") (pinfunction "-_GND@2") (pintype "power_in"))
      (node (ref "C1") (pin "2") (pinfunction "2_2") (pintype "passive"))
      (node (ref "C10") (pin "2") (pinfunction "2_2") (pintype "passive"))
      (node (ref "C12") (pin "-") (pinfunction "-_-") (pintype "passive"))
      (node (ref "C13") (pin "2") (pinfunction "2_2") (pintype "passive"))
      (node (ref "C14") (pin "2") (pinfunction "2_2") (pintype "passive"))
      (node (ref "C16") (pin "2") (pinfunction "2_2") (pintype "passive"))
      (node (ref "C17") (pin "2") (pinfunction "2_2") (pintype "passive"))
      (node (ref "C2") (pin "2") (pinfunction "2_2") (pintype "passive"))
      (node (ref "C3") (pin "2") (pinfunction "2_2") (pintype "passive"))
      (node (ref "C4") (pin "2") (pinfunction "2_2") (pintype "passive"))
      (node (ref "C5") (pin "2") (pinfunction "2_2") (pintype "passive"))
      (node (ref "C6") (pin "2") (pinfunction "2_2") (pintype "passive"))
      (node (ref "C7") (pin "2") (pinfunction "2_2") (pintype "passive"))
      (node (ref "C8") (pin "2") (pinfunction "2_2") (pintype "passive"))
      (node (ref "C9") (pin "2") (pinfunction "2_2") (pintype "passive"))
      (node (ref "CON1") (pin "BASE@1") (pinfunction "GND_BASE@1") (pintype "power_in"))
      (node (ref "CON1") (pin "BASE@2") (pinfunction "GND_BASE@2") (pintype "power_in"))
      (node (ref "CON1") (pin "GND") (pinfunction "GND_GND") (pintype "power_in"))
      (node (ref "CON1") (pin "SPRT@1") (pinfunction "GND_SPRT@1") (pintype "power_in"))
      (node (ref "CON1") (pin "SPRT@2") (pinfunction "GND_SPRT@2") (pintype "power_in"))
      (node (ref "CON1") (pin "SPRT@3") (pinfunction "GND_SPRT@3") (pintype "power_in"))
      (node (ref "CON1") (pin "SPRT@4") (pinfunction "GND_SPRT@4") (pintype "power_in"))
      (node (ref "GND") (pin "1") (pinfunction "1_1") (pintype "passive"))
      (node (ref "GND.") (pin "1") (pinfunction "1_1") (pintype "passive"))
      (node (ref "GND..") (pin "1") (pinfunction "1_1") (pintype "passive"))
      (node (ref "J1") (pin "13") (pinfunction "13_13") (pintype "bidirectional"))
      (node (ref "J1") (pin "14") (pinfunction "14_14") (pintype "bidirectional"))
      (node (ref "J1") (pin "15") (pinfunction "15_15") (pintype "bidirectional"))
      (node (ref "J1") (pin "18") (pinfunction "18_18") (pintype "bidirectional"))
      (node (ref "J1") (pin "3") (pinfunction "3_3") (pintype "bidirectional"))
      (node (ref "J1") (pin "4") (pinfunction "4_4") (pintype "bidirectional"))
      (node (ref "J1") (pin "8") (pinfunction "8_8") (pintype "bidirectional"))
      (node (ref "LED2") (pin "C") (pinfunction "C_C") (pintype "passive"))
      (node (ref "R2") (pin "1") (pinfunction "1_1") (pintype "passive"))
      (node (ref "R5") (pin "1") (pinfunction "1_1") (pintype "passive"))
      (node (ref "R6") (pin "2") (pinfunction "2_2") (pintype "passive"))
      (node (ref "R9") (pin "1") (pinfunction "1_1") (pintype "passive"))
      (node (ref "S1") (pin "P1") (pinfunction "P$1_P1") (pintype "bidirectional"))
      (node (ref "S2") (pin "P1") (pinfunction "P$1_P1") (pintype "bidirectional"))
      (node (ref "SW1") (pin "3") (pinfunction "3_3") (pintype "passive"))
      (node (ref "SW1") (pin "4") (pinfunction "4_4") (pintype "passive"))
      (node (ref "U1") (pin "P$12") (pinfunction "GND_P$12") (pintype "bidirectional"))
      (node (ref "U1") (pin "P$19") (pinfunction "GND_P$19") (pintype "bidirectional"))
      (node (ref "U1") (pin "P$3") (pinfunction "GND_P$3") (pintype "bidirectional"))
      (node (ref "U1") (pin "P$8") (pinfunction "GND_P$8") (pintype "bidirectional"))
      (node (ref "U2") (pin "2") (pinfunction "GND_2") (pintype "power_in"))
      (node (ref "U3") (pin "11") (pinfunction "GND_2_11") (pintype "passive"))
      (node (ref "U3") (pin "6") (pinfunction "VSEL_6") (pintype "input"))
      (node (ref "U3") (pin "8") (pinfunction "GND_8") (pintype "passive"))
      (node (ref "U4") (pin "3") (pinfunction "GND_3") (pintype "bidirectional"))
      (node (ref "U5") (pin "18") (pinfunction "GND_18") (pintype "power_in"))
      (node (ref "U5") (pin "35") (pinfunction "GND_35") (pintype "power_in"))
      (node (ref "U5") (pin "42") (pinfunction "GND_42") (pintype "power_in"))
      (node (ref "U5") (pin "5") (pinfunction "GNDA_5") (pintype "power_in"))
      (node (ref "U5") (pin "THERMAL") (pinfunction "GND_THERMAL") (pintype "power_in"))
      (node (ref "X1") (pin "1") (pinfunction "GND_1") (pintype "passive"))
      (node (ref "X1") (pin "2") (pinfunction "GND_2") (pintype "passive"))
    )
    (net (code "28") (name "LTC3225_VOUT") (class "Default")
      (node (ref "C11") (pin "+") (pinfunction "+_+") (pintype "passive"))
      (node (ref "C16") (pin "1") (pinfunction "1_1") (pintype "passive"))
      (node (ref "J1") (pin "1") (pinfunction "1_1") (pintype "bidirectional"))
      (node (ref "J1") (pin "2") (pinfunction "2_2") (pintype "bidirectional"))
      (node (ref "U3") (pin "10") (pinfunction "COUT_10") (pintype "output"))
    )
    (net (code "29") (name "MISO") (class "Default")
      (node (ref "MISO") (pin "1") (pinfunction "1_1") (pintype "passive"))
      (node (ref "U5") (pin "21") (pinfunction "PA12/I12/I2C/SERCOM2+4.0_21") (pintype "bidirectional"))
    )
    (net (code "30") (name "MOSI") (class "Default")
      (node (ref "MOSI") (pin "1") (pinfunction "1_1") (pintype "passive"))
      (node (ref "U5") (pin "19") (pinfunction "PB10/I10/SERCOM4.2/I2SMC_19") (pintype "bidirectional"))
    )
    (net (code "31") (name "Net-(BAT1---PadGND@1)") (class "Default")
      (node (ref "BAT1") (pin "GND@1") (pinfunction "-_GND@1") (pintype "power_in"))
      (node (ref "BAT1") (pin "GND@2") (pinfunction "-_GND@2") (pintype "power_in"))
      (node (ref "BAT2") (pin "PWR@1") (pinfunction "+_PWR@1") (pintype "power_in"))
      (node (ref "BAT2") (pin "PWR@2") (pinfunction "+_PWR@2") (pintype "power_in"))
    )
    (net (code "32") (name "Net-(BAT2---PadGND@1)") (class "Default")
      (node (ref "BAT2") (pin "GND@1") (pinfunction "-_GND@1") (pintype "power_in"))
      (node (ref "BAT2") (pin "GND@2") (pinfunction "-_GND@2") (pintype "power_in"))
      (node (ref "BAT3") (pin "PWR@1") (pinfunction "+_PWR@1") (pintype "power_in"))
      (node (ref "BAT3") (pin "PWR@2") (pinfunction "+_PWR@2") (pintype "power_in"))
    )
    (net (code "33") (name "Net-(LED1-PadC)") (class "Default")
      (node (ref "LED1") (pin "C") (pinfunction "C_C") (pintype "passive"))
      (node (ref "R5") (pin "2") (pinfunction "2_2") (pintype "passive"))
    )
    (net (code "34") (name "Net-(LED2-PadA)") (class "Default")
      (node (ref "LED2") (pin "A") (pinfunction "A_A") (pintype "passive"))
      (node (ref "R7") (pin "2") (pinfunction "2_2") (pintype "passive"))
    )
    (net (code "35") (name "Net-(U1-EX_ANT)") (class "Default")
      (node (ref "U1") (pin "P$11") (pinfunction "EX_ANT_P$11") (pintype "bidirectional"))
      (node (ref "X1") (pin "3") (pinfunction "SIGNAL_3") (pintype "passive"))
    )
    (net (code "36") (name "Net-(U3-C+)") (class "Default")
      (node (ref "C15") (pin "1") (pinfunction "1_1") (pintype "passive"))
      (node (ref "U3") (pin "1") (pinfunction "C+_1") (pintype "passive"))
    )
    (net (code "37") (name "Net-(U3-C-)") (class "Default")
      (node (ref "C15") (pin "2") (pinfunction "2_2") (pintype "passive"))
      (node (ref "U3") (pin "2") (pinfunction "C-_2") (pintype "passive"))
    )
    (net (code "38") (name "Net-(U3-CX)") (class "Default")
      (node (ref "C11") (pin "-") (pinfunction "-_-") (pintype "passive"))
      (node (ref "C12") (pin "+") (pinfunction "+_+") (pintype "passive"))
      (node (ref "U3") (pin "3") (pinfunction "CX_3") (pintype "passive"))
    )
    (net (code "39") (name "Net-(U3-PROG)") (class "Default")
      (node (ref "R2") (pin "2") (pinfunction "2_2") (pintype "passive"))
      (node (ref "U3") (pin "7") (pinfunction "PROG_7") (pintype "input"))
    )
    (net (code "40") (name "Net-(U4-CAP)") (class "Default")
      (node (ref "C13") (pin "1") (pinfunction "1_1") (pintype "passive"))
      (node (ref "U4") (pin "2") (pinfunction "CAP_2") (pintype "bidirectional"))
    )
    (net (code "41") (name "Net-(U5-PA00{slash}EINT0{slash}SERCOM1.0)") (class "Default")
      (node (ref "C2") (pin "1") (pinfunction "1_1") (pintype "passive"))
      (node (ref "U5") (pin "1") (pinfunction "PA00/EINT0/SERCOM1.0_1") (pintype "bidirectional"))
      (node (ref "X2") (pin "P$1") (pinfunction "P$1_P$1") (pintype "bidirectional"))
    )
    (net (code "42") (name "Net-(U5-PA01{slash}EINT1{slash}SERCOM1.1)") (class "Default")
      (node (ref "C4") (pin "1") (pinfunction "1_1") (pintype "passive"))
      (node (ref "U5") (pin "2") (pinfunction "PA01/EINT1/SERCOM1.1_2") (pintype "bidirectional"))
      (node (ref "X2") (pin "P$2") (pinfunction "P$2_P$2") (pintype "bidirectional"))
    )
    (net (code "43") (name "Net-(U5-VDDCORE)") (class "Default")
      (node (ref "C1") (pin "1") (pinfunction "1_1") (pintype "passive"))
      (node (ref "U5") (pin "43") (pinfunction "VDDCORE_43") (pintype "power_in"))
    )
    (net (code "44") (name "SCK") (class "Default")
      (node (ref "SCK") (pin "1") (pinfunction "1_1") (pintype "passive"))
      (node (ref "U5") (pin "20") (pinfunction "PB11/I11/SERCOM4.3/I2SCL_20") (pintype "bidirectional"))
    )
    (net (code "45") (name "SCL") (class "Default")
      (node (ref "R8") (pin "2") (pinfunction "2_2") (pintype "passive"))
      (node (ref "SCL") (pin "1") (pinfunction "1_1") (pintype "passive"))
      (node (ref "U4") (pin "8") (pinfunction "SCL_8") (pintype "bidirectional"))
      (node (ref "U5") (pin "32") (pinfunction "PA23/I2C/I7/SERCOM3+5.1/SOF_32") (pintype "bidirectional"))
    )
    (net (code "46") (name "SDA") (class "Default")
      (node (ref "R10") (pin "2") (pinfunction "2_2") (pintype "passive"))
      (node (ref "SDA") (pin "1") (pinfunction "1_1") (pintype "passive"))
      (node (ref "U4") (pin "7") (pinfunction "SDA_7") (pintype "bidirectional"))
      (node (ref "U5") (pin "31") (pinfunction "PA22/I2C/I6/SERCOM3+5.0_31") (pintype "bidirectional"))
    )
    (net (code "47") (name "SD_CS") (class "Default")
      (node (ref "SD_CS") (pin "1") (pinfunction "1_1") (pintype "passive"))
      (node (ref "U5") (pin "13") (pinfunction "PA08/I2C/AIN16/SERCOM0+2.0/I2SD1_13") (pintype "bidirectional"))
    )
    (net (code "48") (name "SWCLK") (class "Default")
      (node (ref "SWCLK") (pin "1") (pinfunction "1_1") (pintype "passive"))
      (node (ref "U5") (pin "45") (pinfunction "PA30/I10/SECOM1.2/SWCLK_45") (pintype "bidirectional"))
    )
    (net (code "49") (name "SWDIO") (class "Default")
      (node (ref "SWDIO") (pin "1") (pinfunction "1_1") (pintype "passive"))
      (node (ref "U5") (pin "46") (pinfunction "PA31/I11/SECOM1.3/SWDIO_46") (pintype "bidirectional"))
    )
    (net (code "50") (name "VBAT") (class "Default")
      (node (ref "BAT+") (pin "1") (pinfunction "1_1") (pintype "passive"))
      (node (ref "BAT1") (pin "PWR@1") (pinfunction "+_PWR@1") (pintype "power_in"))
      (node (ref "BAT1") (pin "PWR@2") (pinfunction "+_PWR@2") (pintype "power_in"))
      (node (ref "C17") (pin "1") (pinfunction "1_1") (pintype "passive"))
      (node (ref "D1") (pin "A") (pinfunction "A_A") (pintype "passive"))
      (node (ref "R3") (pin "1") (pinfunction "1_1") (pintype "passive"))
      (node (ref "U3") (pin "9") (pinfunction "VIN_9") (pintype "power_in"))
    )
    (net (code "51") (name "VBUS") (class "Default")
      (node (ref "C6") (pin "1") (pinfunction "1_1") (pintype "passive"))
      (node (ref "CON1") (pin "VBUS") (pinfunction "VBUS_VBUS") (pintype "power_in"))
      (node (ref "D1") (pin "C") (pinfunction "C_C") (pintype "passive"))
      (node (ref "R1") (pin "1") (pinfunction "1_1") (pintype "passive"))
      (node (ref "U2") (pin "1") (pinfunction "IN_1") (pintype "power_in"))
    )
    (net (code "52") (name "unconnected-(CON1-PadID)") (class "Default")
      (node (ref "CON1") (pin "ID") (pinfunction "ID_ID") (pintype "bidirectional"))
    )
    (net (code "53") (name "unconnected-(J1-Pad9)") (class "Default")
      (node (ref "J1") (pin "9") (pinfunction "9_9") (pintype "bidirectional"))
    )
    (net (code "54") (name "unconnected-(J1-Pad10)") (class "Default")
      (node (ref "J1") (pin "10") (pinfunction "10_10") (pintype "bidirectional"))
    )
    (net (code "55") (name "unconnected-(J1-Pad11)") (class "Default")
      (node (ref "J1") (pin "11") (pinfunction "11_11") (pintype "bidirectional"))
    )
    (net (code "56") (name "unconnected-(J1-Pad12)") (class "Default")
      (node (ref "J1") (pin "12") (pinfunction "12_12") (pintype "bidirectional"))
    )
    (net (code "57") (name "unconnected-(J1-Pad16)") (class "Default")
      (node (ref "J1") (pin "16") (pinfunction "16_16") (pintype "bidirectional"))
    )
    (net (code "58") (name "unconnected-(J1-Pad17)") (class "Default")
      (node (ref "J1") (pin "17") (pinfunction "17_17") (pintype "bidirectional"))
    )
    (net (code "59") (name "unconnected-(J1-Pad20)") (class "Default")
      (node (ref "J1") (pin "20") (pinfunction "20_20") (pintype "bidirectional"))
    )
    (net (code "60") (name "unconnected-(U1-1PPS-PadP$13)") (class "Default")
      (node (ref "U1") (pin "P$13") (pinfunction "1PPS_P$13") (pintype "bidirectional"))
    )
    (net (code "61") (name "unconnected-(U1-NC-PadP$6)") (class "Default")
      (node (ref "U1") (pin "P$6") (pinfunction "NC_P$6") (pintype "bidirectional"))
    )
    (net (code "62") (name "unconnected-(U1-NC-PadP$7)") (class "Default")
      (node (ref "U1") (pin "P$7") (pinfunction "NC_P$7") (pintype "bidirectional"))
    )
    (net (code "63") (name "unconnected-(U1-NC-PadP$15)") (class "Default")
      (node (ref "U1") (pin "P$15") (pinfunction "NC_P$15") (pintype "bidirectional"))
    )
    (net (code "64") (name "unconnected-(U1-NC-PadP$16)") (class "Default")
      (node (ref "U1") (pin "P$16") (pinfunction "NC_P$16") (pintype "bidirectional"))
    )
    (net (code "65") (name "unconnected-(U1-NC-PadP$17)") (class "Default")
      (node (ref "U1") (pin "P$17") (pinfunction "NC_P$17") (pintype "bidirectional"))
    )
    (net (code "66") (name "unconnected-(U1-NC-PadP$18)") (class "Default")
      (node (ref "U1") (pin "P$18") (pinfunction "NC_P$18") (pintype "bidirectional"))
    )
    (net (code "67") (name "unconnected-(U1-NC-PadP$20)") (class "Default")
      (node (ref "U1") (pin "P$20") (pinfunction "NC_P$20") (pintype "bidirectional"))
    )
    (net (code "68") (name "unconnected-(U1-NRESET-PadP$2)") (class "Default")
      (node (ref "U1") (pin "P$2") (pinfunction "NRESET_P$2") (pintype "bidirectional"))
    )
    (net (code "69") (name "unconnected-(U1-RTCM-PadP$14)") (class "Default")
      (node (ref "U1") (pin "P$14") (pinfunction "RTCM_P$14") (pintype "bidirectional"))
    )
    (net (code "70") (name "unconnected-(U2-P4-Pad4)") (class "Default")
      (node (ref "U2") (pin "4") (pinfunction "P4_4") (pintype "bidirectional"))
    )
    (net (code "71") (name "unconnected-(U4-INT1-Pad6)") (class "Default")
      (node (ref "U4") (pin "6") (pinfunction "INT1_6") (pintype "bidirectional"))
    )
    (net (code "72") (name "unconnected-(U4-INT2-Pad5)") (class "Default")
      (node (ref "U4") (pin "5") (pinfunction "INT2_5") (pintype "bidirectional"))
    )
    (net (code "73") (name "unconnected-(U5-PA13{slash}I13{slash}I2C{slash}SERCOM2+4.1-Pad22)") (class "Default")
      (node (ref "U5") (pin "22") (pinfunction "PA13/I13/I2C/SERCOM2+4.1_22") (pintype "bidirectional"))
    )
    (net (code "74") (name "unconnected-(U5-PA27{slash}I15-Pad39)") (class "Default")
      (node (ref "U5") (pin "39") (pinfunction "PA27/I15_39") (pintype "bidirectional"))
    )
    (net (code "75") (name "unconnected-(U5-PA28{slash}I8-Pad41)") (class "Default")
      (node (ref "U5") (pin "41") (pinfunction "PA28/I8_41") (pintype "bidirectional"))
    )
    (net (code "76") (name "unconnected-(U5-PB03{slash}I3{slash}AIN11{slash}SERCOM5.1-Pad48)") (class "Default")
      (node (ref "U5") (pin "48") (pinfunction "PB03/I3/AIN11/SERCOM5.1_48") (pintype "bidirectional"))
    )
    (net (code "77") (name "unconnected-(U5-PB22{slash}I6{slash}SERCOM5.2-Pad37)") (class "Default")
      (node (ref "U5") (pin "37") (pinfunction "PB22/I6/SERCOM5.2_37") (pintype "bidirectional"))
    )
    (net (code "78") (name "unconnected-(U5-PB23{slash}I7{slash}SERCOM5.3-Pad38)") (class "Default")
      (node (ref "U5") (pin "38") (pinfunction "PB23/I7/SERCOM5.3_38") (pintype "bidirectional"))
    )
    (net (code "79") (name "~{RESET}") (class "Default")
      (node (ref "SW1") (pin "1") (pinfunction "1_1") (pintype "passive"))
      (node (ref "SW1") (pin "2") (pinfunction "2_2") (pintype "passive"))
      (node (ref "U5") (pin "40") (pinfunction "/RESET_40") (pintype "bidirectional"))
    )
  )
)
